# current.net
KiCad netlist of a schematic drawn in EAGLE
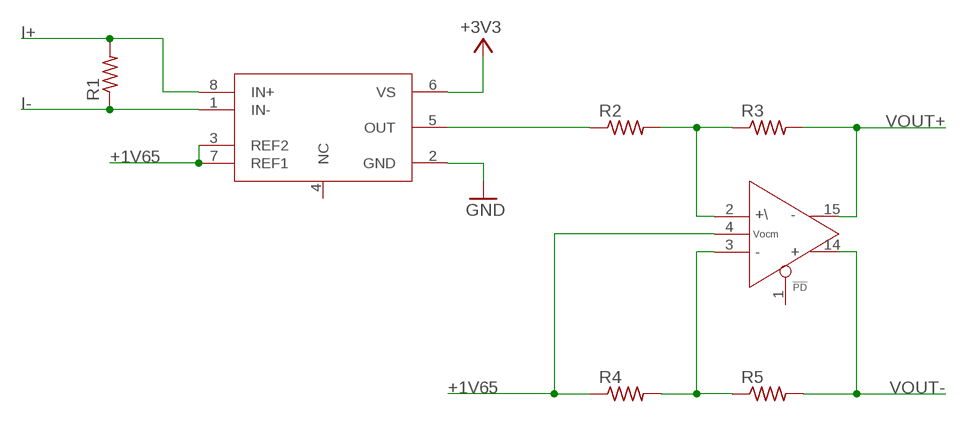
[diagram p0: schematic, sheet 1]

(export (version "E")
  (design (tool "Eeschema 10.0.6"))
  (components
    (comp (ref "R1")
      (value "R-US_R0805")
      (footprint "eagle-import:R0805")
      (libsource (lib "eagle-import") (part "R-US_R0805"))
    )
    (comp (ref "R2")
      (value "R-US_R0805")
      (footprint "eagle-import:R0805")
      (libsource (lib "eagle-import") (part "R-US_R0805"))
    )
    (comp (ref "R3")
      (value "R-US_R0805")
      (footprint "eagle-import:R0805")
      (libsource (lib "eagle-import") (part "R-US_R0805"))
    )
    (comp (ref "R4")
      (value "R-US_R0805")
      (footprint "eagle-import:R0805")
      (libsource (lib "eagle-import") (part "R-US_R0805"))
    )
    (comp (ref "R5")
      (value "R-US_R0805")
      (footprint "eagle-import:R0805")
      (libsource (lib "eagle-import") (part "R-US_R0805"))
    )
    (comp (ref "U1")
      (value "INA296A5")
      (footprint "eagle-import:SOT23_DDF_TEX")
      (fields
        (field (name "MANUFACTURER_PART_NUMBER") "PINA296A2IDDFR")
        (field (name "COPYRIGHT") "Copyright (C) 2023 Ultra Librarian. All rights reserved.")
      )
      (libsource (lib "eagle-import") (part "INA296A5"))
    )
    (comp (ref "U2")
      (value "THS4532IPW")
      (footprint "eagle-import:SOP65P640X120-16N")
      (fields (field (name "DIGI-KEY_PART_NUMBER") "296-39813-5-ND") (field (name "MF") "Texas Instruments"))
      (libsource (lib "eagle-import") (part "THS4532IPW"))
    )
  )
  (nets
    (net (code "1") (name "+3V3") (class "Default")
      (node (ref "U1") (pin "6") (pinfunction "VS_6") (pintype "power_in"))
    )
    (net (code "2") (name "/+1V65") (class "Default")
      (node (ref "R4") (pin "1") (pinfunction "1_1") (pintype "passive"))
      (node (ref "U1") (pin "3") (pinfunction "REF2_3") (pintype "bidirectional"))
      (node (ref "U1") (pin "7") (pinfunction "REF1_7") (pintype "bidirectional"))
      (node (ref "U2") (pin "4") (pinfunction "VOCM_4") (pintype "passive"))
    )
    (net (code "3") (name "/I+") (class "Default")
      (node (ref "R1") (pin "2") (pinfunction "2_2") (pintype "passive"))
      (node (ref "U1") (pin "8") (pinfunction "IN+_8") (pintype "input"))
    )
    (net (code "4") (name "/I-") (class "Default")
      (node (ref "R1") (pin "1") (pinfunction "1_1") (pintype "passive"))
      (node (ref "U1") (pin "1") (pinfunction "IN-_1") (pintype "input"))
    )
    (net (code "5") (name "/VOUT+") (class "Default")
      (node (ref "R3") (pin "2") (pinfunction "2_2") (pintype "passive"))
      (node (ref "U2") (pin "15") (pinfunction "OUT-_15") (pintype "output"))
    )
    (net (code "6") (name "/VOUT-") (class "Default")
      (node (ref "R5") (pin "2") (pinfunction "2_2") (pintype "passive"))
      (node (ref "U2") (pin "14") (pinfunction "OUT+_14") (pintype "output"))
    )
    (net (code "7") (name "GND") (class "Default")
      (node (ref "U1") (pin "2") (pinfunction "GND_2") (pintype "passive"))
    )
    (net (code "8") (name "Net-(U1-OUT)") (class "Default")
      (node (ref "R2") (pin "1") (pinfunction "1_1") (pintype "passive"))
      (node (ref "U1") (pin "5") (pinfunction "OUT_5") (pintype "output"))
    )
    (net (code "9") (name "Net-(U2A-+IN)") (class "Default")
      (node (ref "R2") (pin "2") (pinfunction "2_2") (pintype "passive"))
      (node (ref "R3") (pin "1") (pinfunction "1_1") (pintype "passive"))
      (node (ref "U2") (pin "2") (pinfunction "+IN_2") (pintype "input"))
    )
    (net (code "10") (name "Net-(U2A--IN)") (class "Default")
      (node (ref "R4") (pin "2") (pinfunction "2_2") (pintype "passive"))
      (node (ref "R5") (pin "1") (pinfunction "1_1") (pintype "passive"))
      (node (ref "U2") (pin "3") (pinfunction "-IN_3") (pintype "input"))
    )
    (net (code "11") (name "unconnected-(U1-NC-Pad4)") (class "Default")
      (node (ref "U1") (pin "4") (pinfunction "NC_4") (pintype "no_connect"))
    )
    (net (code "12") (name "unconnected-(U2A-~{PD}-Pad1)") (class "Default")
      (node (ref "U2") (pin "1") (pinfunction "~{PD}_1") (pintype "passive"))
    )
  )
)
